# Sensor-ToF.net
KiCad netlist of a schematic drawn in Altium Designer
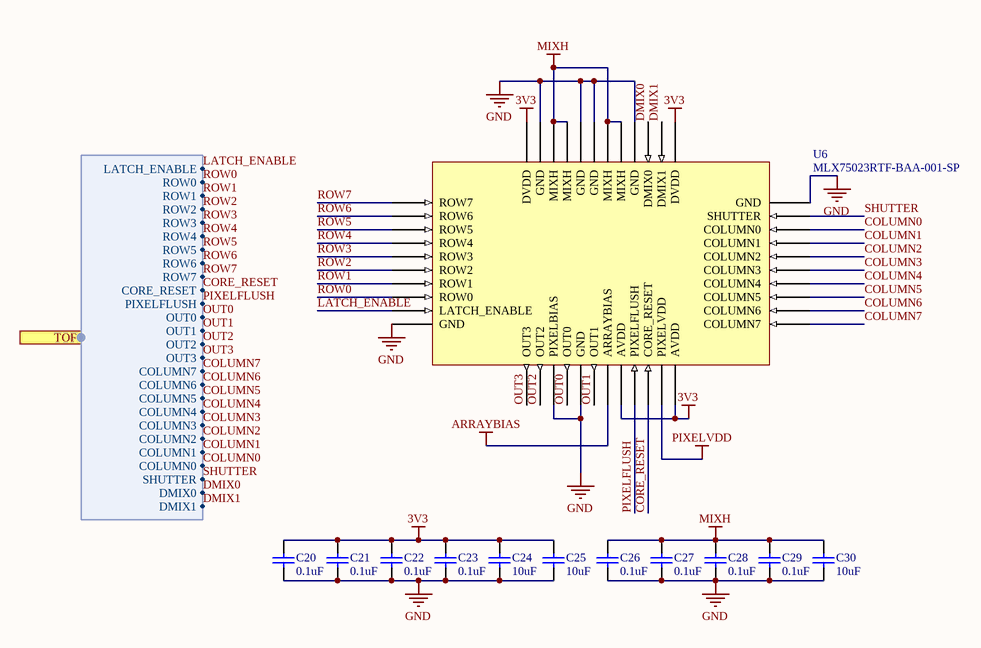
[diagram p0: Sensor-ToF.SchDoc]

(export (version "E")
  (design (tool "Eeschema 10.0.6"))
  (components
    (comp (ref "C20")
      (value "0.1uF")
      (footprint "C0201[0603X30]")
      (description "0.1uF 6.3V 10% 0201 (0603 Metric)")
      (fields (field (name "PARTNUMBER") "GRT033R60J104KE01D") (field (name "MANUFACTURER") "Murata"))
      (libsource (lib "Capacitors") (part "CAP_0.1uF_6.3V_0201_10%"))
    )
    (comp (ref "C21")
      (value "0.1uF")
      (footprint "C0201[0603X30]")
      (description "0.1uF 6.3V 10% 0201 (0603 Metric)")
      (fields (field (name "PARTNUMBER") "GRT033R60J104KE01D") (field (name "MANUFACTURER") "Murata"))
      (libsource (lib "Capacitors") (part "CAP_0.1uF_6.3V_0201_10%"))
    )
    (comp (ref "C22")
      (value "0.1uF")
      (footprint "C0201[0603X30]")
      (description "0.1uF 6.3V 10% 0201 (0603 Metric)")
      (fields (field (name "PARTNUMBER") "GRT033R60J104KE01D") (field (name "MANUFACTURER") "Murata"))
      (libsource (lib "Capacitors") (part "CAP_0.1uF_6.3V_0201_10%"))
    )
    (comp (ref "C23")
      (value "0.1uF")
      (footprint "C0201[0603X30]")
      (description "0.1uF 6.3V 10% 0201 (0603 Metric)")
      (fields (field (name "PARTNUMBER") "GRT033R60J104KE01D") (field (name "MANUFACTURER") "Murata"))
      (libsource (lib "Capacitors") (part "CAP_0.1uF_6.3V_0201_10%"))
    )
    (comp (ref "C24")
      (value "10uF")
      (footprint "C0402[1005X55]")
      (description "10uF 6.3V 20% 0402 (1005 Metric)")
      (fields (field (name "PARTNUMBER") "GRM155R60J106ME44D") (field (name "MANUFACTURER") "Murata"))
      (libsource (lib "Capacitors") (part "CAP_10uF_6.3V_0402_20%"))
    )
    (comp (ref "C25")
      (value "10uF")
      (footprint "C0402[1005X55]")
      (description "10uF 6.3V 20% 0402 (1005 Metric)")
      (fields (field (name "PARTNUMBER") "GRM155R60J106ME44D") (field (name "MANUFACTURER") "Murata"))
      (libsource (lib "Capacitors") (part "CAP_10uF_6.3V_0402_20%"))
    )
    (comp (ref "C26")
      (value "0.1uF")
      (footprint "C0201[0603X30]")
      (description "0.1uF 6.3V 10% 0201 (0603 Metric)")
      (fields (field (name "PARTNUMBER") "GRT033R60J104KE01D") (field (name "MANUFACTURER") "Murata"))
      (libsource (lib "Capacitors") (part "CAP_0.1uF_6.3V_0201_10%"))
    )
    (comp (ref "C27")
      (value "0.1uF")
      (footprint "C0201[0603X30]")
      (description "0.1uF 6.3V 10% 0201 (0603 Metric)")
      (fields (field (name "PARTNUMBER") "GRT033R60J104KE01D") (field (name "MANUFACTURER") "Murata"))
      (libsource (lib "Capacitors") (part "CAP_0.1uF_6.3V_0201_10%"))
    )
    (comp (ref "C28")
      (value "0.1uF")
      (footprint "C0201[0603X30]")
      (description "0.1uF 6.3V 10% 0201 (0603 Metric)")
      (fields (field (name "PARTNUMBER") "GRT033R60J104KE01D") (field (name "MANUFACTURER") "Murata"))
      (libsource (lib "Capacitors") (part "CAP_0.1uF_6.3V_0201_10%"))
    )
    (comp (ref "C29")
      (value "0.1uF")
      (footprint "C0201[0603X30]")
      (description "0.1uF 6.3V 10% 0201 (0603 Metric)")
      (fields (field (name "PARTNUMBER") "GRT033R60J104KE01D") (field (name "MANUFACTURER") "Murata"))
      (libsource (lib "Capacitors") (part "CAP_0.1uF_6.3V_0201_10%"))
    )
    (comp (ref "C30")
      (value "10uF")
      (footprint "C0402[1005X55]")
      (description "10uF 6.3V 20% 0402 (1005 Metric)")
      (fields (field (name "PARTNUMBER") "GRM155R60J106ME44D") (field (name "MANUFACTURER") "Murata"))
      (libsource (lib "Capacitors") (part "CAP_10uF_6.3V_0402_20%"))
    )
    (comp (ref "U6")
      (value "MLX75023RTF-BAA-001-SP")
      (footprint "BGA-44")
      (fields (field (name "MANUFACTURER") "Melexis"))
      (libsource (lib "ICs") (part "MLX75023RTF-BAA-001-SP"))
    )
  )
  (nets
    (net (code "2") (name "/COLUMN0") (class "Default")
      (node (ref "U6") (pin "30") (pinfunction "COLUMN0_30") (pintype "input"))
    )
    (net (code "3") (name "/COLUMN1") (class "Default")
      (node (ref "U6") (pin "29") (pinfunction "COLUMN1_29") (pintype "input"))
    )
    (net (code "4") (name "/COLUMN2") (class "Default")
      (node (ref "U6") (pin "28") (pinfunction "COLUMN2_28") (pintype "input"))
    )
    (net (code "5") (name "/COLUMN3") (class "Default")
      (node (ref "U6") (pin "27") (pinfunction "COLUMN3_27") (pintype "input"))
    )
    (net (code "6") (name "/COLUMN4") (class "Default")
      (node (ref "U6") (pin "26") (pinfunction "COLUMN4_26") (pintype "input"))
    )
    (net (code "7") (name "/COLUMN5") (class "Default")
      (node (ref "U6") (pin "25") (pinfunction "COLUMN5_25") (pintype "input"))
    )
    (net (code "8") (name "/COLUMN6") (class "Default")
      (node (ref "U6") (pin "24") (pinfunction "COLUMN6_24") (pintype "input"))
    )
    (net (code "9") (name "/COLUMN7") (class "Default")
      (node (ref "U6") (pin "23") (pinfunction "COLUMN7_23") (pintype "input"))
    )
    (net (code "10") (name "/CORE_RESET") (class "Default")
      (node (ref "U6") (pin "20") (pinfunction "CORE_RESET_20") (pintype "input"))
    )
    (net (code "11") (name "/DMIX0") (class "Default")
      (node (ref "U6") (pin "35") (pinfunction "DMIX0_35") (pintype "input"))
    )
    (net (code "12") (name "/DMIX1") (class "Default")
      (node (ref "U6") (pin "34") (pinfunction "DMIX1_34") (pintype "input"))
    )
    (net (code "13") (name "/LATCH_ENABLE") (class "Default")
      (node (ref "U6") (pin "9") (pinfunction "LATCH_ENABLE_9") (pintype "input"))
    )
    (net (code "14") (name "/OUT0") (class "Default")
      (node (ref "U6") (pin "14") (pinfunction "OUT0_14") (pintype "output"))
    )
    (net (code "15") (name "/OUT1") (class "Default")
      (node (ref "U6") (pin "16") (pinfunction "OUT1_16") (pintype "output"))
    )
    (net (code "16") (name "/OUT2") (class "Default")
      (node (ref "U6") (pin "12") (pinfunction "OUT2_12") (pintype "output"))
    )
    (net (code "17") (name "/OUT3") (class "Default")
      (node (ref "U6") (pin "11") (pinfunction "OUT3_11") (pintype "output"))
    )
    (net (code "18") (name "/PIXELFLUSH") (class "Default")
      (node (ref "U6") (pin "19") (pinfunction "PIXELFLUSH_19") (pintype "input"))
    )
    (net (code "19") (name "/ROW0") (class "Default")
      (node (ref "U6") (pin "8") (pinfunction "ROW0_8") (pintype "input"))
    )
    (net (code "20") (name "/ROW1") (class "Default")
      (node (ref "U6") (pin "7") (pinfunction "ROW1_7") (pintype "input"))
    )
    (net (code "21") (name "/ROW2") (class "Default")
      (node (ref "U6") (pin "6") (pinfunction "ROW2_6") (pintype "input"))
    )
    (net (code "22") (name "/ROW3") (class "Default")
      (node (ref "U6") (pin "5") (pinfunction "ROW3_5") (pintype "input"))
    )
    (net (code "23") (name "/ROW4") (class "Default")
      (node (ref "U6") (pin "4") (pinfunction "ROW4_4") (pintype "input"))
    )
    (net (code "24") (name "/ROW5") (class "Default")
      (node (ref "U6") (pin "3") (pinfunction "ROW5_3") (pintype "input"))
    )
    (net (code "25") (name "/ROW6") (class "Default")
      (node (ref "U6") (pin "2") (pinfunction "ROW6_2") (pintype "input"))
    )
    (net (code "26") (name "/ROW7") (class "Default")
      (node (ref "U6") (pin "1") (pinfunction "ROW7_1") (pintype "input"))
    )
    (net (code "27") (name "/SHUTTER") (class "Default")
      (node (ref "U6") (pin "31") (pinfunction "SHUTTER_31") (pintype "input"))
    )
    (net (code "29") (name "3V3") (class "Default")
      (node (ref "C20") (pin "2") (pinfunction "2_2") (pintype "passive"))
      (node (ref "C21") (pin "2") (pinfunction "2_2") (pintype "passive"))
      (node (ref "C22") (pin "2") (pinfunction "2_2") (pintype "passive"))
      (node (ref "C23") (pin "2") (pinfunction "2_2") (pintype "passive"))
      (node (ref "C24") (pin "2") (pinfunction "2_2") (pintype "passive"))
      (node (ref "C25") (pin "2") (pinfunction "2_2") (pintype "passive"))
      (node (ref "U6") (pin "18") (pinfunction "AVDD_18") (pintype "power_in"))
      (node (ref "U6") (pin "22") (pinfunction "AVDD_22") (pintype "power_in"))
      (node (ref "U6") (pin "33") (pinfunction "DVDD_33") (pintype "power_in"))
      (node (ref "U6") (pin "44") (pinfunction "DVDD_44") (pintype "power_in"))
    )
    (net (code "30") (name "ARRAYBIAS") (class "Default")
      (node (ref "U6") (pin "17") (pinfunction "ARRAYBIAS_17") (pintype "passive"))
    )
    (net (code "31") (name "GND") (class "Default")
      (node (ref "C20") (pin "1") (pinfunction "1_1") (pintype "passive"))
      (node (ref "C21") (pin "1") (pinfunction "1_1") (pintype "passive"))
      (node (ref "C22") (pin "1") (pinfunction "1_1") (pintype "passive"))
      (node (ref "C23") (pin "1") (pinfunction "1_1") (pintype "passive"))
      (node (ref "C24") (pin "1") (pinfunction "1_1") (pintype "passive"))
      (node (ref "C25") (pin "1") (pinfunction "1_1") (pintype "passive"))
      (node (ref "C26") (pin "1") (pinfunction "1_1") (pintype "passive"))
      (node (ref "C27") (pin "1") (pinfunction "1_1") (pintype "passive"))
      (node (ref "C28") (pin "1") (pinfunction "1_1") (pintype "passive"))
      (node (ref "C29") (pin "1") (pinfunction "1_1") (pintype "passive"))
      (node (ref "C30") (pin "1") (pinfunction "1_1") (pintype "passive"))
      (node (ref "U6") (pin "10") (pinfunction "GND_10") (pintype "power_in"))
      (node (ref "U6") (pin "13") (pinfunction "PIXELBIAS_13") (pintype "passive"))
      (node (ref "U6") (pin "15") (pinfunction "GND_15") (pintype "power_in"))
      (node (ref "U6") (pin "32") (pinfunction "GND_32") (pintype "power_in"))
      (node (ref "U6") (pin "36") (pinfunction "GND_36") (pintype "power_in"))
      (node (ref "U6") (pin "39") (pinfunction "GND_39") (pintype "power_in"))
      (node (ref "U6") (pin "40") (pinfunction "GND_40") (pintype "power_in"))
      (node (ref "U6") (pin "43") (pinfunction "GND_43") (pintype "power_in"))
    )
    (net (code "32") (name "MIXH") (class "Default")
      (node (ref "C26") (pin "2") (pinfunction "2_2") (pintype "passive"))
      (node (ref "C27") (pin "2") (pinfunction "2_2") (pintype "passive"))
      (node (ref "C28") (pin "2") (pinfunction "2_2") (pintype "passive"))
      (node (ref "C29") (pin "2") (pinfunction "2_2") (pintype "passive"))
      (node (ref "C30") (pin "2") (pinfunction "2_2") (pintype "passive"))
      (node (ref "U6") (pin "37") (pinfunction "MIXH_37") (pintype "power_in"))
      (node (ref "U6") (pin "38") (pinfunction "MIXH_38") (pintype "power_in"))
      (node (ref "U6") (pin "41") (pinfunction "MIXH_41") (pintype "power_in"))
      (node (ref "U6") (pin "42") (pinfunction "MIXH_42") (pintype "power_in"))
    )
    (net (code "33") (name "PIXELVDD") (class "Default")
      (node (ref "U6") (pin "21") (pinfunction "PIXELVDD_21") (pintype "power_in"))
    )
  )
)
